# Hydra.net
KiCad netlist of a schematic drawn in EAGLE
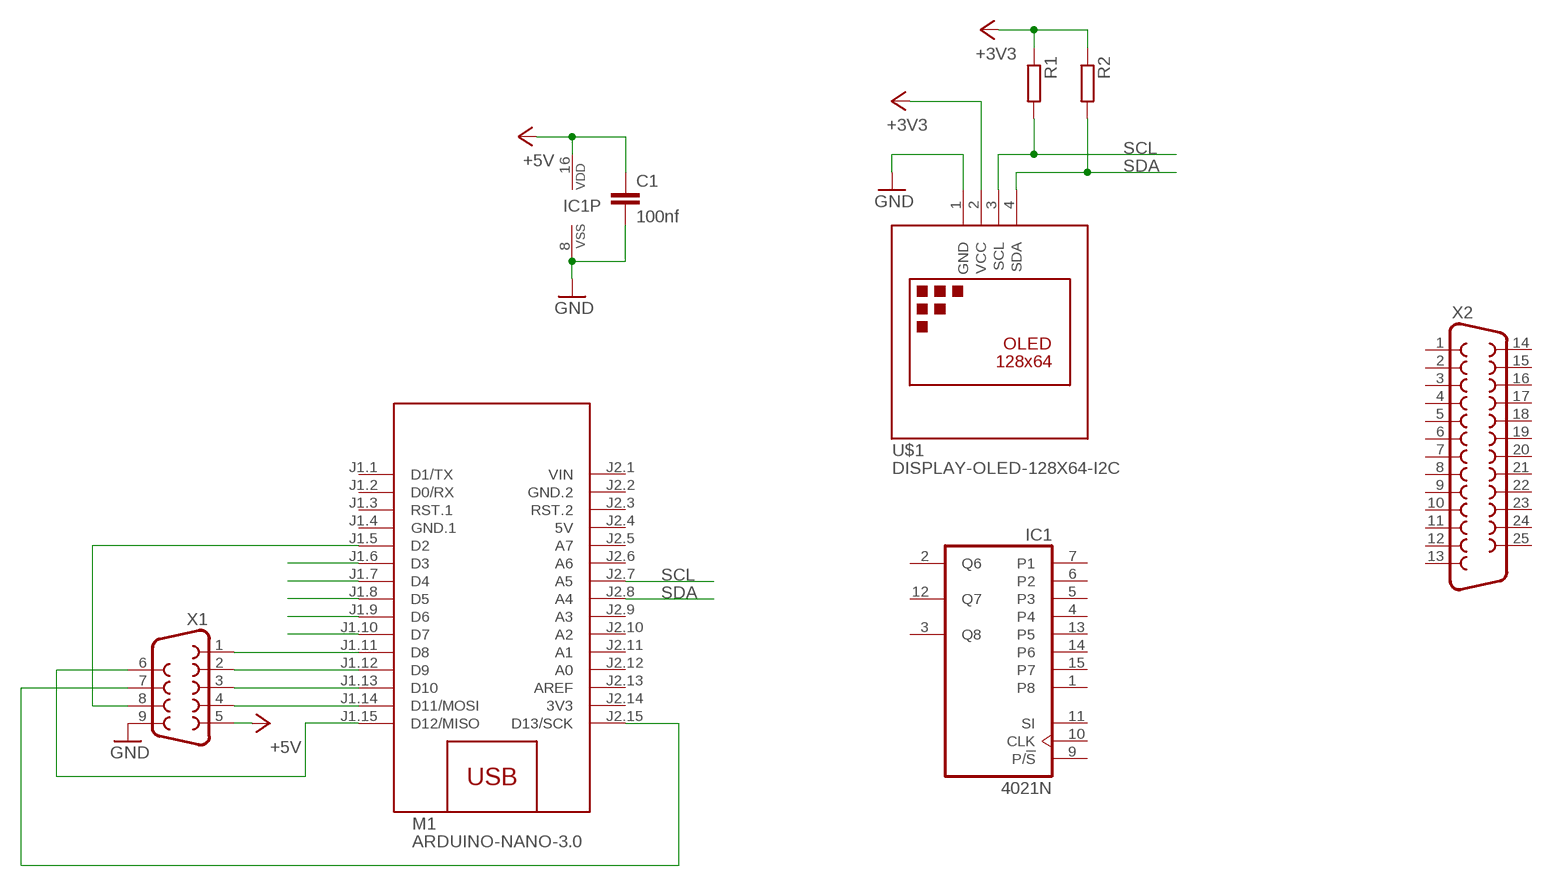
[diagram p0: schematic, sheet 1]

(export (version "E")
  (design (tool "Eeschema 10.0.6"))
  (components
    (comp (ref "C1")
      (value "100nf")
      (footprint "eagle-import:C050-024X044")
      (libsource (lib "eagle-import") (part "C-EU050-024X044"))
    )
    (comp (ref "IC1")
      (value "4021N")
      (footprint "eagle-import:DIL16")
      (libsource (lib "eagle-import") (part "4021N"))
    )
    (comp (ref "M1")
      (value "ARDUINO-NANO-3.0")
      (footprint "eagle-import:ARDUINO-NANO-3.0")
      (libsource (lib "eagle-import") (part "ARDUINO-NANO-3.0"))
    )
    (comp (ref "R1")
      (value "R-EU_0204/5")
      (footprint "eagle-import:0204_5")
      (libsource (lib "eagle-import") (part "R-EU_0204/5"))
    )
    (comp (ref "R2")
      (value "R-EU_0204/5")
      (footprint "eagle-import:0204_5")
      (libsource (lib "eagle-import") (part "R-EU_0204/5"))
    )
    (comp (ref "U$1")
      (value "DISPLAY-OLED-128X64-I2C")
      (footprint "eagle-import:DISPLAY-OLED-128X64-I2C")
      (libsource (lib "eagle-import") (part "DISPLAY-OLED-128X64-I2C"))
    )
    (comp (ref "X1")
      (value "F09D")
      (footprint "eagle-import:F09D")
      (libsource (lib "eagle-import") (part "F09D"))
    )
    (comp (ref "X2")
      (value "F25D")
      (footprint "eagle-import:F25D")
      (libsource (lib "eagle-import") (part "F25D"))
    )
  )
  (nets
    (net (code "1") (name "+3V3") (class "Default")
      (node (ref "R1") (pin "1") (pinfunction "1_1") (pintype "passive"))
      (node (ref "R2") (pin "1") (pinfunction "1_1") (pintype "passive"))
      (node (ref "U$1") (pin "2") (pinfunction "VCC_2") (pintype "power_in"))
    )
    (net (code "2") (name "+5V") (class "Default")
      (node (ref "C1") (pin "1") (pinfunction "1_1") (pintype "passive"))
      (node (ref "IC1") (pin "16") (pinfunction "VDD_16") (pintype "power_in"))
      (node (ref "X1") (pin "5") (pinfunction "5_5") (pintype "passive"))
    )
    (net (code "3") (name "/3V3") (class "Default")
      (node (ref "M1") (pin "J2.14") (pinfunction "3V3_J2.14") (pintype "power_in"))
    )
    (net (code "4") (name "/5V") (class "Default")
      (node (ref "M1") (pin "J2.4") (pinfunction "5V_J2.4") (pintype "power_in"))
    )
    (net (code "5") (name "/GND.1") (class "Default")
      (node (ref "M1") (pin "J1.4") (pinfunction "GND.1_J1.4") (pintype "power_in"))
    )
    (net (code "6") (name "/GND.2") (class "Default")
      (node (ref "M1") (pin "J2.2") (pinfunction "GND.2_J2.2") (pintype "power_in"))
    )
    (net (code "7") (name "/SCL") (class "Default")
      (node (ref "M1") (pin "J2.7") (pinfunction "A5_J2.7") (pintype "bidirectional"))
      (node (ref "R1") (pin "2") (pinfunction "2_2") (pintype "passive"))
      (node (ref "U$1") (pin "3") (pinfunction "SCL_3") (pintype "bidirectional"))
    )
    (net (code "8") (name "/SDA") (class "Default")
      (node (ref "M1") (pin "J2.8") (pinfunction "A4_J2.8") (pintype "bidirectional"))
      (node (ref "R2") (pin "2") (pinfunction "2_2") (pintype "passive"))
      (node (ref "U$1") (pin "4") (pinfunction "SDA_4") (pintype "bidirectional"))
    )
    (net (code "9") (name "/VIN") (class "Default")
      (node (ref "M1") (pin "J2.1") (pinfunction "VIN_J2.1") (pintype "power_in"))
    )
    (net (code "10") (name "GND") (class "Default")
      (node (ref "C1") (pin "2") (pinfunction "2_2") (pintype "passive"))
      (node (ref "IC1") (pin "8") (pinfunction "VSS_8") (pintype "power_in"))
      (node (ref "U$1") (pin "1") (pinfunction "GND_1") (pintype "power_in"))
      (node (ref "X1") (pin "9") (pinfunction "9_9") (pintype "passive"))
    )
    (net (code "11") (name "Net-(M1-D2)") (class "Default")
      (node (ref "M1") (pin "J1.5") (pinfunction "D2_J1.5") (pintype "bidirectional"))
      (node (ref "X1") (pin "8") (pinfunction "8_8") (pintype "passive"))
    )
    (net (code "12") (name "Net-(M1-D8)") (class "Default")
      (node (ref "M1") (pin "J1.11") (pinfunction "D8_J1.11") (pintype "bidirectional"))
      (node (ref "X1") (pin "1") (pinfunction "1_1") (pintype "passive"))
    )
    (net (code "13") (name "Net-(M1-D9)") (class "Default")
      (node (ref "M1") (pin "J1.12") (pinfunction "D9_J1.12") (pintype "bidirectional"))
      (node (ref "X1") (pin "2") (pinfunction "2_2") (pintype "passive"))
    )
    (net (code "14") (name "Net-(M1-D10)") (class "Default")
      (node (ref "M1") (pin "J1.13") (pinfunction "D10_J1.13") (pintype "bidirectional"))
      (node (ref "X1") (pin "3") (pinfunction "3_3") (pintype "passive"))
    )
    (net (code "15") (name "Net-(M1-D11{slash}MOSI)") (class "Default")
      (node (ref "M1") (pin "J1.14") (pinfunction "D11/MOSI_J1.14") (pintype "bidirectional"))
      (node (ref "X1") (pin "4") (pinfunction "4_4") (pintype "passive"))
    )
    (net (code "16") (name "Net-(M1-D12{slash}MISO)") (class "Default")
      (node (ref "M1") (pin "J1.15") (pinfunction "D12/MISO_J1.15") (pintype "bidirectional"))
      (node (ref "X1") (pin "6") (pinfunction "6_6") (pintype "passive"))
    )
    (net (code "17") (name "Net-(M1-D13{slash}SCK)") (class "Default")
      (node (ref "M1") (pin "J2.15") (pinfunction "D13/SCK_J2.15") (pintype "bidirectional"))
      (node (ref "X1") (pin "7") (pinfunction "7_7") (pintype "passive"))
    )
    (net (code "18") (name "unconnected-(IC1A-CLK-Pad10)") (class "Default")
      (node (ref "IC1") (pin "10") (pinfunction "CLK_10") (pintype "input"))
    )
    (net (code "19") (name "unconnected-(IC1A-P1-Pad7)") (class "Default")
      (node (ref "IC1") (pin "7") (pinfunction "P1_7") (pintype "input"))
    )
    (net (code "20") (name "unconnected-(IC1A-P2-Pad6)") (class "Default")
      (node (ref "IC1") (pin "6") (pinfunction "P2_6") (pintype "input"))
    )
    (net (code "21") (name "unconnected-(IC1A-P3-Pad5)") (class "Default")
      (node (ref "IC1") (pin "5") (pinfunction "P3_5") (pintype "input"))
    )
    (net (code "22") (name "unconnected-(IC1A-P4-Pad4)") (class "Default")
      (node (ref "IC1") (pin "4") (pinfunction "P4_4") (pintype "input"))
    )
    (net (code "23") (name "unconnected-(IC1A-P5-Pad13)") (class "Default")
      (node (ref "IC1") (pin "13") (pinfunction "P5_13") (pintype "input"))
    )
    (net (code "24") (name "unconnected-(IC1A-P6-Pad14)") (class "Default")
      (node (ref "IC1") (pin "14") (pinfunction "P6_14") (pintype "input"))
    )
    (net (code "25") (name "unconnected-(IC1A-P7-Pad15)") (class "Default")
      (node (ref "IC1") (pin "15") (pinfunction "P7_15") (pintype "input"))
    )
    (net (code "26") (name "unconnected-(IC1A-P8-Pad1)") (class "Default")
      (node (ref "IC1") (pin "1") (pinfunction "P8_1") (pintype "input"))
    )
    (net (code "27") (name "unconnected-(IC1A-P{slash}~{S}-Pad9)") (class "Default")
      (node (ref "IC1") (pin "9") (pinfunction "P/~{S}_9") (pintype "input"))
    )
    (net (code "28") (name "unconnected-(IC1A-Q6-Pad2)") (class "Default")
      (node (ref "IC1") (pin "2") (pinfunction "Q6_2") (pintype "output"))
    )
    (net (code "29") (name "unconnected-(IC1A-Q7-Pad12)") (class "Default")
      (node (ref "IC1") (pin "12") (pinfunction "Q7_12") (pintype "output"))
    )
    (net (code "30") (name "unconnected-(IC1A-Q8-Pad3)") (class "Default")
      (node (ref "IC1") (pin "3") (pinfunction "Q8_3") (pintype "output"))
    )
    (net (code "31") (name "unconnected-(IC1A-SI-Pad11)") (class "Default")
      (node (ref "IC1") (pin "11") (pinfunction "SI_11") (pintype "input"))
    )
    (net (code "32") (name "unconnected-(M1-A0-PadJ2.12)") (class "Default")
      (node (ref "M1") (pin "J2.12") (pinfunction "A0_J2.12") (pintype "bidirectional"))
    )
    (net (code "33") (name "unconnected-(M1-A1-PadJ2.11)") (class "Default")
      (node (ref "M1") (pin "J2.11") (pinfunction "A1_J2.11") (pintype "bidirectional"))
    )
    (net (code "34") (name "unconnected-(M1-A2-PadJ2.10)") (class "Default")
      (node (ref "M1") (pin "J2.10") (pinfunction "A2_J2.10") (pintype "bidirectional"))
    )
    (net (code "35") (name "unconnected-(M1-A3-PadJ2.9)") (class "Default")
      (node (ref "M1") (pin "J2.9") (pinfunction "A3_J2.9") (pintype "bidirectional"))
    )
    (net (code "36") (name "unconnected-(M1-A6-PadJ2.6)") (class "Default")
      (node (ref "M1") (pin "J2.6") (pinfunction "A6_J2.6") (pintype "bidirectional"))
    )
    (net (code "37") (name "unconnected-(M1-A7-PadJ2.5)") (class "Default")
      (node (ref "M1") (pin "J2.5") (pinfunction "A7_J2.5") (pintype "bidirectional"))
    )
    (net (code "38") (name "unconnected-(M1-AREF-PadJ2.13)") (class "Default")
      (node (ref "M1") (pin "J2.13") (pinfunction "AREF_J2.13") (pintype "bidirectional"))
    )
    (net (code "39") (name "unconnected-(M1-D0{slash}RX-PadJ1.2)") (class "Default")
      (node (ref "M1") (pin "J1.2") (pinfunction "D0/RX_J1.2") (pintype "bidirectional"))
    )
    (net (code "40") (name "unconnected-(M1-D1{slash}TX-PadJ1.1)") (class "Default")
      (node (ref "M1") (pin "J1.1") (pinfunction "D1/TX_J1.1") (pintype "bidirectional"))
    )
    (net (code "41") (name "unconnected-(M1-D3-PadJ1.6)") (class "Default")
      (node (ref "M1") (pin "J1.6") (pinfunction "D3_J1.6") (pintype "bidirectional"))
    )
    (net (code "42") (name "unconnected-(M1-D4-PadJ1.7)") (class "Default")
      (node (ref "M1") (pin "J1.7") (pinfunction "D4_J1.7") (pintype "bidirectional"))
    )
    (net (code "43") (name "unconnected-(M1-D5-PadJ1.8)") (class "Default")
      (node (ref "M1") (pin "J1.8") (pinfunction "D5_J1.8") (pintype "bidirectional"))
    )
    (net (code "44") (name "unconnected-(M1-D6-PadJ1.9)") (class "Default")
      (node (ref "M1") (pin "J1.9") (pinfunction "D6_J1.9") (pintype "bidirectional"))
    )
    (net (code "45") (name "unconnected-(M1-D7-PadJ1.10)") (class "Default")
      (node (ref "M1") (pin "J1.10") (pinfunction "D7_J1.10") (pintype "bidirectional"))
    )
    (net (code "46") (name "unconnected-(M1-RST.1-PadJ1.3)") (class "Default")
      (node (ref "M1") (pin "J1.3") (pinfunction "RST.1_J1.3") (pintype "bidirectional"))
    )
    (net (code "47") (name "unconnected-(M1-RST.2-PadJ2.3)") (class "Default")
      (node (ref "M1") (pin "J2.3") (pinfunction "RST.2_J2.3") (pintype "bidirectional"))
    )
    (net (code "48") (name "unconnected-(X2-Pad1)") (class "Default")
      (node (ref "X2") (pin "1") (pinfunction "1_1") (pintype "passive"))
    )
    (net (code "49") (name "unconnected-(X2-Pad2)") (class "Default")
      (node (ref "X2") (pin "2") (pinfunction "2_2") (pintype "passive"))
    )
    (net (code "50") (name "unconnected-(X2-Pad3)") (class "Default")
      (node (ref "X2") (pin "3") (pinfunction "3_3") (pintype "passive"))
    )
    (net (code "51") (name "unconnected-(X2-Pad4)") (class "Default")
      (node (ref "X2") (pin "4") (pinfunction "4_4") (pintype "passive"))
    )
    (net (code "52") (name "unconnected-(X2-Pad5)") (class "Default")
      (node (ref "X2") (pin "5") (pinfunction "5_5") (pintype "passive"))
    )
    (net (code "53") (name "unconnected-(X2-Pad6)") (class "Default")
      (node (ref "X2") (pin "6") (pinfunction "6_6") (pintype "passive"))
    )
    (net (code "54") (name "unconnected-(X2-Pad7)") (class "Default")
      (node (ref "X2") (pin "7") (pinfunction "7_7") (pintype "passive"))
    )
    (net (code "55") (name "unconnected-(X2-Pad8)") (class "Default")
      (node (ref "X2") (pin "8") (pinfunction "8_8") (pintype "passive"))
    )
    (net (code "56") (name "unconnected-(X2-Pad9)") (class "Default")
      (node (ref "X2") (pin "9") (pinfunction "9_9") (pintype "passive"))
    )
    (net (code "57") (name "unconnected-(X2-Pad10)") (class "Default")
      (node (ref "X2") (pin "10") (pinfunction "10_10") (pintype "passive"))
    )
    (net (code "58") (name "unconnected-(X2-Pad11)") (class "Default")
      (node (ref "X2") (pin "11") (pinfunction "11_11") (pintype "passive"))
    )
    (net (code "59") (name "unconnected-(X2-Pad12)") (class "Default")
      (node (ref "X2") (pin "12") (pinfunction "12_12") (pintype "passive"))
    )
    (net (code "60") (name "unconnected-(X2-Pad13)") (class "Default")
      (node (ref "X2") (pin "13") (pinfunction "13_13") (pintype "passive"))
    )
    (net (code "61") (name "unconnected-(X2-Pad14)") (class "Default")
      (node (ref "X2") (pin "14") (pinfunction "14_14") (pintype "passive"))
    )
    (net (code "62") (name "unconnected-(X2-Pad15)") (class "Default")
      (node (ref "X2") (pin "15") (pinfunction "15_15") (pintype "passive"))
    )
    (net (code "63") (name "unconnected-(X2-Pad16)") (class "Default")
      (node (ref "X2") (pin "16") (pinfunction "16_16") (pintype "passive"))
    )
    (net (code "64") (name "unconnected-(X2-Pad17)") (class "Default")
      (node (ref "X2") (pin "17") (pinfunction "17_17") (pintype "passive"))
    )
    (net (code "65") (name "unconnected-(X2-Pad18)") (class "Default")
      (node (ref "X2") (pin "18") (pinfunction "18_18") (pintype "passive"))
    )
    (net (code "66") (name "unconnected-(X2-Pad19)") (class "Default")
      (node (ref "X2") (pin "19") (pinfunction "19_19") (pintype "passive"))
    )
    (net (code "67") (name "unconnected-(X2-Pad20)") (class "Default")
      (node (ref "X2") (pin "20") (pinfunction "20_20") (pintype "passive"))
    )
    (net (code "68") (name "unconnected-(X2-Pad21)") (class "Default")
      (node (ref "X2") (pin "21") (pinfunction "21_21") (pintype "passive"))
    )
    (net (code "69") (name "unconnected-(X2-Pad22)") (class "Default")
      (node (ref "X2") (pin "22") (pinfunction "22_22") (pintype "passive"))
    )
    (net (code "70") (name "unconnected-(X2-Pad23)") (class "Default")
      (node (ref "X2") (pin "23") (pinfunction "23_23") (pintype "passive"))
    )
    (net (code "71") (name "unconnected-(X2-Pad24)") (class "Default")
      (node (ref "X2") (pin "24") (pinfunction "24_24") (pintype "passive"))
    )
    (net (code "72") (name "unconnected-(X2-Pad25)") (class "Default")
      (node (ref "X2") (pin "25") (pinfunction "25_25") (pintype "passive"))
    )
  )
)
